# smd.net
KiCad netlist of a schematic drawn in EAGLE
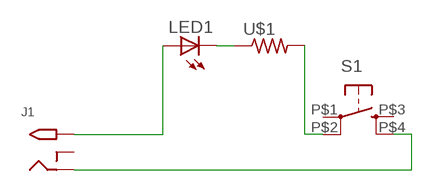
[diagram p0: schematic, sheet 1]

(export (version "E")
  (design (tool "Eeschema 10.0.6"))
  (components
    (comp (ref "J1")
      (value "2.1MMJACKTHM")
      (footprint "eagle-import:PJ-102A")
      (libsource (lib "eagle-import") (part "2.1MMJACKTHM"))
    )
    (comp (ref "LED1")
      (value "LED5MM")
      (footprint "eagle-import:LED5MM")
      (libsource (lib "eagle-import") (part "LED5MM"))
    )
    (comp (ref "S1")
      (value "BUTTON-TACTILE-SMD")
      (footprint "eagle-import:BUTTON-TACTILE-SQUARE_SMD")
      (libsource (lib "eagle-import") (part "BUTTON-TACTILE-SMD"))
    )
    (comp (ref "U$1")
      (value "RESISTORTH-1/4W-CARBON")
      (footprint "eagle-import:RESAD1160W55L680D260_HS")
      (libsource (lib "eagle-import") (part "RESISTORTH-1/4W-CARBON"))
    )
  )
  (nets
    (net (code "1") (name "Net-(J1-PadTIP)") (class "Default")
      (node (ref "J1") (pin "TIP") (pinfunction "TIP_TIP") (pintype "bidirectional"))
      (node (ref "LED1") (pin "A") (pinfunction "A_A") (pintype "passive"))
    )
    (net (code "2") (name "Net-(LED1-C)") (class "Default")
      (node (ref "LED1") (pin "K") (pinfunction "C_K") (pintype "passive"))
      (node (ref "U$1") (pin "1") (pinfunction "1_1") (pintype "passive"))
    )
    (net (code "3") (name "Net-(S1-P1)") (class "Default")
      (node (ref "S1") (pin "P$2") (pinfunction "P1_P$2") (pintype "passive"))
      (node (ref "U$1") (pin "2") (pinfunction "2_2") (pintype "passive"))
    )
    (net (code "4") (name "Net-(S1-S1)") (class "Default")
      (node (ref "J1") (pin "RING") (pinfunction "RING_RING") (pintype "bidirectional"))
      (node (ref "S1") (pin "P$4") (pinfunction "S1_P$4") (pintype "passive"))
    )
    (net (code "5") (name "unconnected-(J1-PadRING_SW)") (class "Default")
      (node (ref "J1") (pin "RING_SW") (pinfunction "RING_SW_RING_SW") (pintype "bidirectional"))
    )
    (net (code "6") (name "unconnected-(S1-P-PadP$1)") (class "Default")
      (node (ref "S1") (pin "P$1") (pinfunction "P_P$1") (pintype "passive"))
    )
    (net (code "7") (name "unconnected-(S1-S-PadP$3)") (class "Default")
      (node (ref "S1") (pin "P$3") (pinfunction "S_P$3") (pintype "passive"))
    )
  )
)
